# Microcontroller.net
KiCad netlist of a schematic drawn in Altium Designer
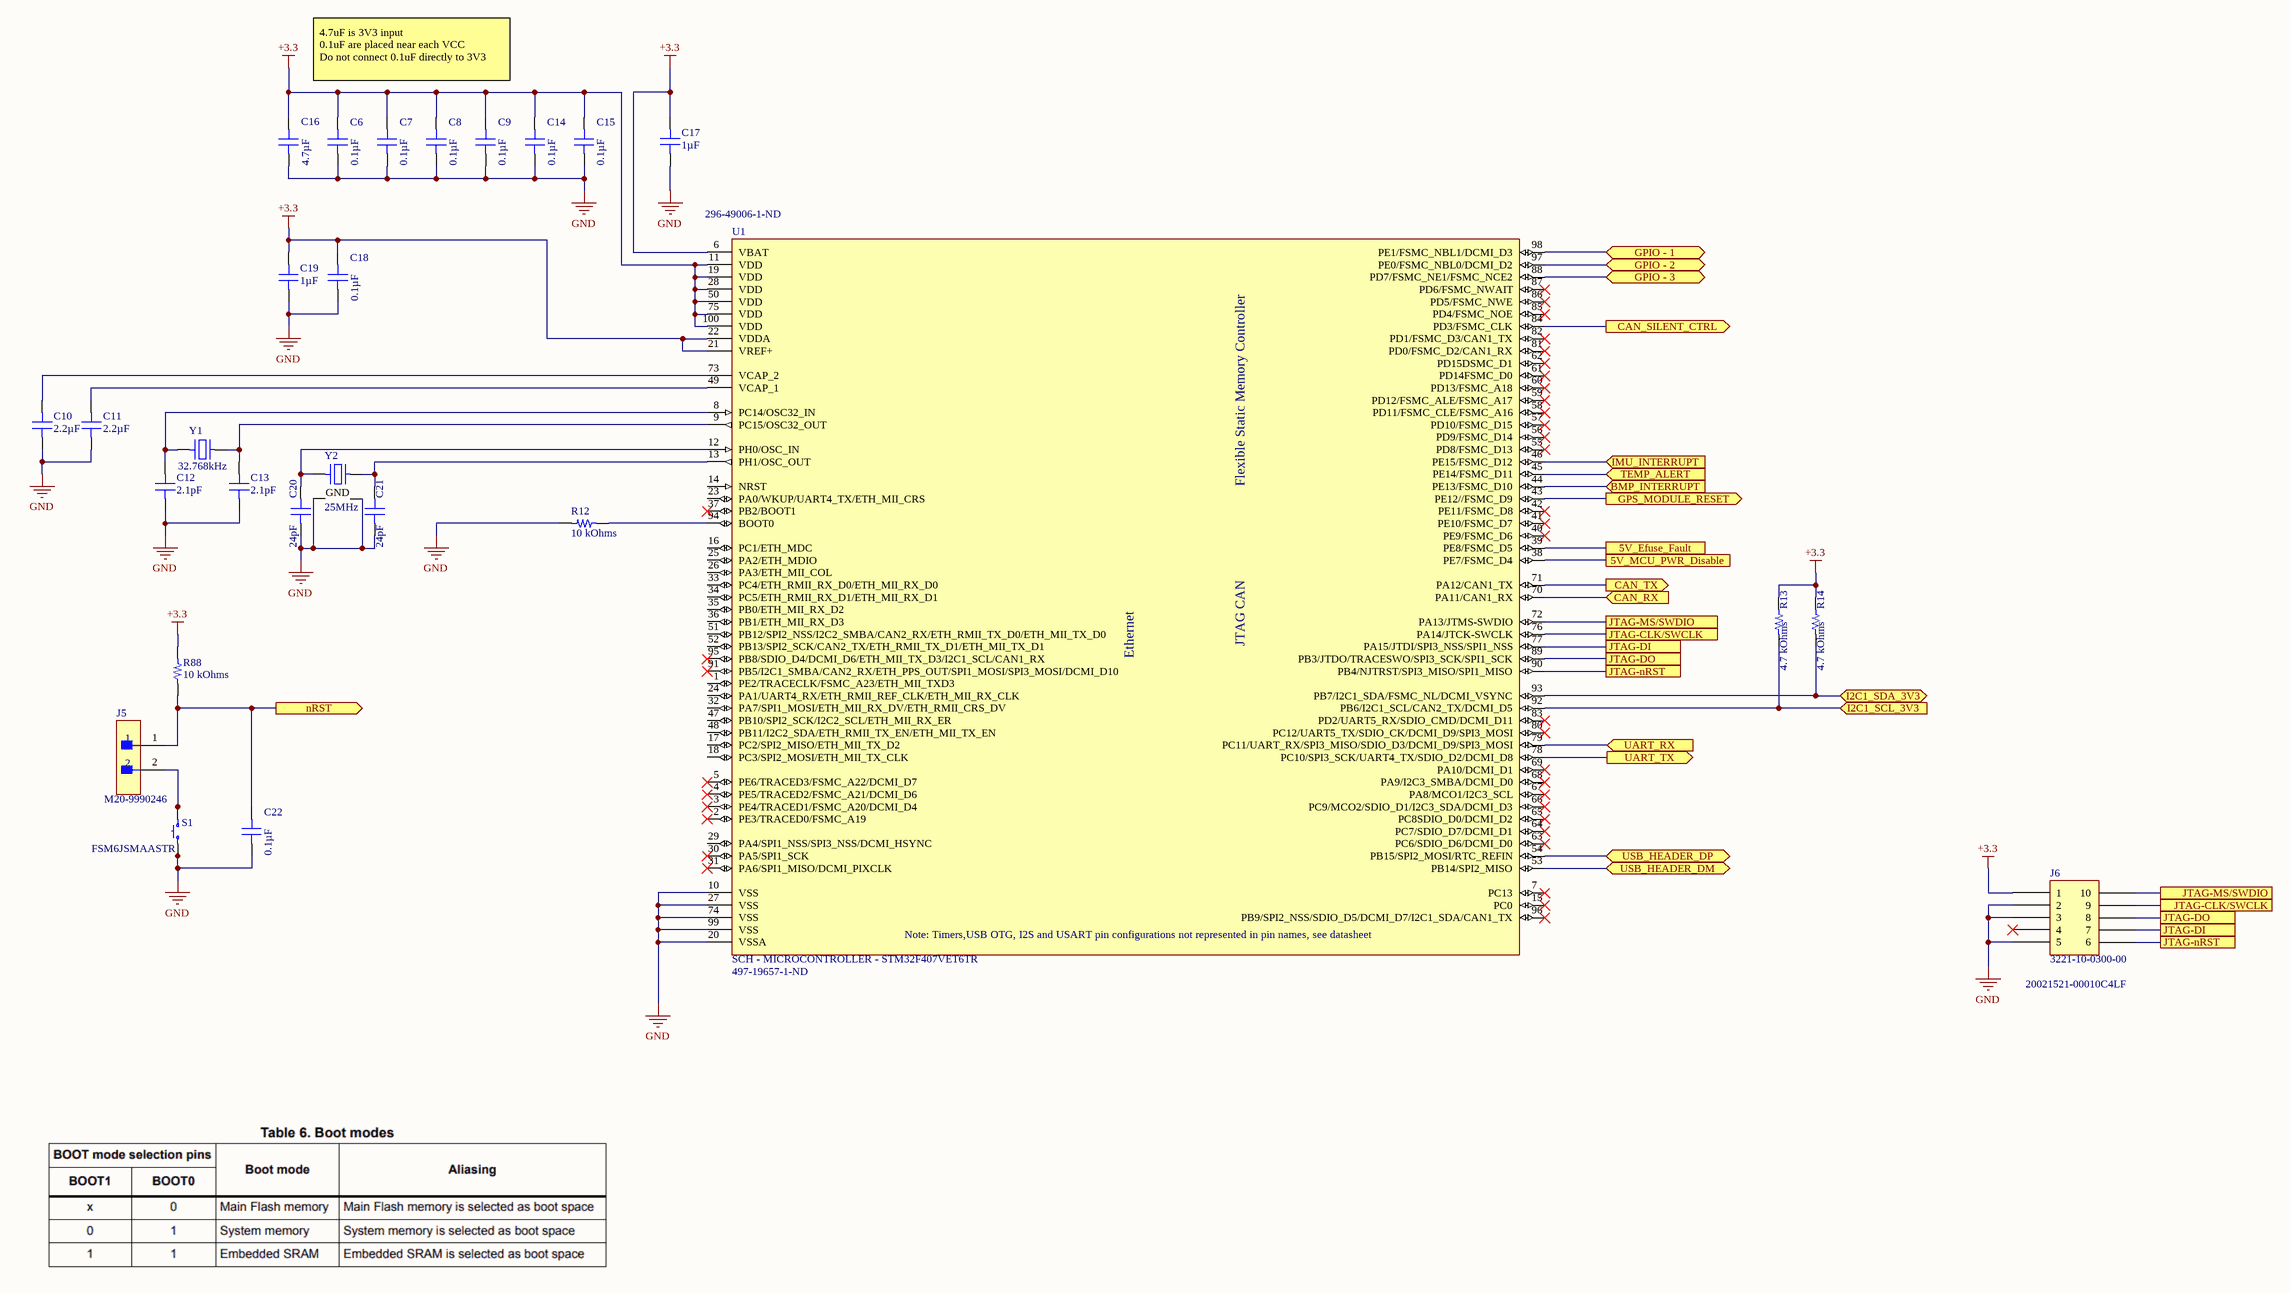
[diagram p0: Microcontroller.SchDoc]

(export (version "E")
  (design (tool "Eeschema 10.0.6"))
  (components
    (comp (ref "C6")
      (value "0.1µF")
      (footprint "CAP 0603_1608")
      (description "CAP CER 0.1UF 25V X7R 0603")
      (fields
        (field (name "PART NUMBER") "CL10B104KA8WPNC")
        (field (name "MANUFACTURER") "Samsung Electro-Mechanics")
      )
      (libsource (lib "Celestial Altium Library - altium_library") (part "Capacitor"))
    )
    (comp (ref "C7")
      (value "0.1µF")
      (footprint "CAP 0603_1608")
      (description "CAP CER 0.1UF 25V X7R 0603")
      (fields
        (field (name "PART NUMBER") "CL10B104KA8WPNC")
        (field (name "MANUFACTURER") "Samsung Electro-Mechanics")
      )
      (libsource (lib "Celestial Altium Library - altium_library") (part "Capacitor"))
    )
    (comp (ref "C8")
      (value "0.1µF")
      (footprint "CAP 0603_1608")
      (description "CAP CER 0.1UF 25V X7R 0603")
      (fields
        (field (name "PART NUMBER") "CL10B104KA8WPNC")
        (field (name "MANUFACTURER") "Samsung Electro-Mechanics")
      )
      (libsource (lib "Celestial Altium Library - altium_library") (part "Capacitor"))
    )
    (comp (ref "C9")
      (value "0.1µF")
      (footprint "CAP 0603_1608")
      (description "CAP CER 0.1UF 25V X7R 0603")
      (fields
        (field (name "PART NUMBER") "CL10B104KA8WPNC")
        (field (name "MANUFACTURER") "Samsung Electro-Mechanics")
      )
      (libsource (lib "Celestial Altium Library - altium_library") (part "Capacitor"))
    )
    (comp (ref "C10")
      (value "2.2µF")
      (footprint "CAP 0603_1608")
      (description "CAP CER 2.2UF 16V X5R 0603")
      (fields (field (name "PART NUMBER") "EMK107BJ225KA-T") (field (name "MANUFACTURER") "Taiyo Yuden"))
      (libsource (lib "Celestial Altium Library - altium_library") (part "Capacitor"))
    )
    (comp (ref "C11")
      (value "2.2µF")
      (footprint "CAP 0603_1608")
      (description "CAP CER 2.2UF 16V X5R 0603")
      (fields (field (name "PART NUMBER") "EMK107BJ225KA-T") (field (name "MANUFACTURER") "Taiyo Yuden"))
      (libsource (lib "Celestial Altium Library - altium_library") (part "Capacitor"))
    )
    (comp (ref "C12")
      (value "2.1pF")
      (footprint "CAP 0603_1608")
      (description "CAP CER RF 2.1PF 50V +/-0.1 PF C")
      (fields (field (name "PART NUMBER") "CBR06C219B5GAC") (field (name "MANUFACTURER") "KEMET"))
      (libsource (lib "Celestial Altium Library - altium_library") (part "Capacitor"))
    )
    (comp (ref "C13")
      (value "2.1pF")
      (footprint "CAP 0603_1608")
      (description "CAP CER RF 2.1PF 50V +/-0.1 PF C")
      (fields (field (name "PART NUMBER") "CBR06C219B5GAC") (field (name "MANUFACTURER") "KEMET"))
      (libsource (lib "Celestial Altium Library - altium_library") (part "Capacitor"))
    )
    (comp (ref "C14")
      (value "0.1µF")
      (footprint "CAP 0603_1608")
      (description "CAP CER 0.1UF 25V X7R 0603")
      (fields
        (field (name "PART NUMBER") "CL10B104KA8WPNC")
        (field (name "MANUFACTURER") "Samsung Electro-Mechanics")
      )
      (libsource (lib "Celestial Altium Library - altium_library") (part "Capacitor"))
    )
    (comp (ref "C15")
      (value "0.1µF")
      (footprint "CAP 0603_1608")
      (description "CAP CER 0.1UF 25V X7R 0603")
      (fields
        (field (name "PART NUMBER") "CL10B104KA8WPNC")
        (field (name "MANUFACTURER") "Samsung Electro-Mechanics")
      )
      (libsource (lib "Celestial Altium Library - altium_library") (part "Capacitor"))
    )
    (comp (ref "C16")
      (value "4.7µF")
      (footprint "CAP 0603_1608")
      (description "CAP CER 4.7UF 16V X5R 0603")
      (fields
        (field (name "PART NUMBER") "C1608X5R1C475K080AC")
        (field (name "MANUFACTURER") "TDK Corporation")
      )
      (libsource (lib "Celestial Altium Library - altium_library") (part "Capacitor"))
    )
    (comp (ref "C17")
      (value "1µF")
      (footprint "CAP 0603_1608")
      (description "CAP CER 1UF 16V X7R 0603")
      (fields
        (field (name "PART NUMBER") "GCM188R71C105KA64J")
        (field (name "MANUFACTURER") "Murata Electronics")
      )
      (libsource (lib "Celestial Altium Library - altium_library") (part "Capacitor"))
    )
    (comp (ref "C18")
      (value "0.1µF")
      (footprint "CAP 0603_1608")
      (description "CAP CER 0.1UF 25V X7R 0603")
      (fields
        (field (name "PART NUMBER") "CL10B104KA8WPNC")
        (field (name "MANUFACTURER") "Samsung Electro-Mechanics")
      )
      (libsource (lib "Celestial Altium Library - altium_library") (part "Capacitor"))
    )
    (comp (ref "C19")
      (value "1µF")
      (footprint "CAP 0603_1608")
      (description "CAP CER 1UF 16V X7R 0603")
      (fields
        (field (name "PART NUMBER") "GCM188R71C105KA64J")
        (field (name "MANUFACTURER") "Murata Electronics")
      )
      (libsource (lib "Celestial Altium Library - altium_library") (part "Capacitor"))
    )
    (comp (ref "C20")
      (value "24pF")
      (footprint "CAP 0603_1608")
      (description "CAP CER 24PF 50V C0G/NP0 0603")
      (fields
        (field (name "PART NUMBER") "CL10C240JB8NNNC")
        (field (name "MANUFACTURER") "Samsung Electro-Mechanics")
      )
      (libsource (lib "Celestial Altium Library - altium_library") (part "Capacitor"))
    )
    (comp (ref "C21")
      (value "24pF")
      (footprint "CAP 0603_1608")
      (description "CAP CER 24PF 50V C0G/NP0 0603")
      (fields
        (field (name "PART NUMBER") "CL10C240JB8NNNC")
        (field (name "MANUFACTURER") "Samsung Electro-Mechanics")
      )
      (libsource (lib "Celestial Altium Library - altium_library") (part "Capacitor"))
    )
    (comp (ref "C22")
      (value "0.1µF")
      (footprint "CAP 0603_1608")
      (description "CAP CER 0.1UF 25V X7R 0603")
      (fields
        (field (name "PART NUMBER") "CL10B104KA8WPNC")
        (field (name "MANUFACTURER") "Samsung Electro-Mechanics")
      )
      (libsource (lib "Celestial Altium Library - altium_library") (part "Capacitor"))
    )
    (comp (ref "J5")
      (value "M20-9990246")
      (footprint "FP-M20-9990246-MFG")
      (description "CONN HEADER VERT 2POS 2.54MM")
      (fields
        (field (name "OCTOPART") "https://octopart.com/m20-9990246-harwin-2590635")
        (field (name "MANUFACTURER") "Harwin")
      )
      (libsource (lib "Altium Content Vault") (part "3bc925449376181038e59eaffc5286c"))
    )
    (comp (ref "J6")
      (value "3221-10-0300-00")
      (footprint "CNC TECH 3221-10-0300-00")
      (description "CONN HEADER SMD 10POS 1.27MM")
      (fields (field (name "MANUFACTURER") "CNC Tech"))
      (libsource (lib "Celestial Altium Library - altium_library") (part "2x5 Pin"))
    )
    (comp (ref "R12")
      (value "10 kOhms")
      (footprint "RES 0603_1608")
      (description "RES 10K OHM 5% 1/10W 0603")
      (fields
        (field (name "PART NUMBER") "RMCF0603JT10K0")
        (field (name "MANUFACTURER") "Stackpole Electronics Inc")
      )
      (libsource (lib "Celestial Altium Library - altium_library") (part "Resistor"))
    )
    (comp (ref "R13")
      (value "4.7 kOhms")
      (footprint "RES 0603_1608")
      (description "RES 4.7K OHM 1% 1/10W 0603")
      (fields
        (field (name "PART NUMBER") "RMCF0603FT4K70")
        (field (name "MANUFACTURER") "Stackpole Electronics Inc")
      )
      (libsource (lib "Celestial Altium Library - altium_library") (part "Resistor"))
    )
    (comp (ref "R14")
      (value "4.7 kOhms")
      (footprint "RES 0603_1608")
      (description "RES 4.7K OHM 1% 1/10W 0603")
      (fields
        (field (name "PART NUMBER") "RMCF0603FT4K70")
        (field (name "MANUFACTURER") "Stackpole Electronics Inc")
      )
      (libsource (lib "Celestial Altium Library - altium_library") (part "Resistor"))
    )
    (comp (ref "R88")
      (value "10 kOhms")
      (footprint "RES 0603_1608")
      (description "RES 10K OHM 5% 1/10W 0603")
      (fields
        (field (name "PART NUMBER") "RMCF0603JT10K0")
        (field (name "MANUFACTURER") "Stackpole Electronics Inc")
      )
      (libsource (lib "Celestial Altium Library - altium_library") (part "Resistor"))
    )
    (comp (ref "S1")
      (value "FSM6JSMAASTR")
      (footprint "TE FSM6JSMA")
      (description "SWITCH TACTILE SPST-NO 0.05A 24V")
      (fields (field (name "MANUFACTURER") "TE Connectivity ALCOSWITCH Switches"))
      (libsource (lib "Celestial Altium Library - altium_library") (part "SPST-NO 4 PIN"))
    )
    (comp (ref "U1")
      (value "SCH - MICROCONTROLLER - STM32F407VET6TR")
      (footprint "PCB - LEADLESS - QFP - ST LQFP-100 14X14MM")
      (fields (field (name "SUPPLIER PART NUMBER 1") "497-19657-1-ND"))
      (libsource (lib "HAB_ICs") (part "SCH - MICROCONTROLLER - STM32F407VET6TR"))
    )
    (comp (ref "Y1")
      (value "32.768kHz")
      (footprint "ABRACON ABS07")
      (description "IOT 32.786KHZ XTAL")
      (fields
        (field (name "PART NUMBER") "ABS07-166-32.768KHZ-T")
        (field (name "MANUFACTURER") "Abracon LLC")
      )
      (libsource (lib "Celestial Altium Library - altium_library") (part "Abracon Crystal ABS07"))
    )
    (comp (ref "Y2")
      (value "25MHz")
      (footprint "EPSON TSX-3225")
      (description "CRYSTAL 25.0000MHZ 18PF SMD")
      (fields (field (name "PART NUMBER") "TSX-3225 25.0000MF20P-C0") (field (name "MANUFACTURER") "EPSON"))
      (libsource (lib "Celestial Altium Library - altium_library") (part "Epson Crystal TSX-3225"))
    )
  )
  (nets
    (net (code "1") (name "+3.3") (class "Default")
      (node (ref "C14") (pin "2") (pinfunction "2_2") (pintype "passive"))
      (node (ref "C15") (pin "2") (pinfunction "2_2") (pintype "passive"))
      (node (ref "C16") (pin "2") (pinfunction "2_2") (pintype "passive"))
      (node (ref "C17") (pin "2") (pinfunction "2_2") (pintype "passive"))
      (node (ref "C18") (pin "2") (pinfunction "2_2") (pintype "passive"))
      (node (ref "C19") (pin "2") (pinfunction "2_2") (pintype "passive"))
      (node (ref "C6") (pin "2") (pinfunction "2_2") (pintype "passive"))
      (node (ref "C7") (pin "2") (pinfunction "2_2") (pintype "passive"))
      (node (ref "C8") (pin "2") (pinfunction "2_2") (pintype "passive"))
      (node (ref "C9") (pin "2") (pinfunction "2_2") (pintype "passive"))
      (node (ref "J6") (pin "1") (pinfunction "1_1") (pintype "passive"))
      (node (ref "R13") (pin "2") (pinfunction "2_2") (pintype "passive"))
      (node (ref "R14") (pin "2") (pinfunction "2_2") (pintype "passive"))
      (node (ref "R88") (pin "1") (pinfunction "1_1") (pintype "passive"))
      (node (ref "U1") (pin "100") (pinfunction "VDD_100") (pintype "power_in"))
      (node (ref "U1") (pin "11") (pinfunction "VDD_11") (pintype "power_in"))
      (node (ref "U1") (pin "19") (pinfunction "VDD_19") (pintype "power_in"))
      (node (ref "U1") (pin "21") (pinfunction "VREF+_21") (pintype "power_in"))
      (node (ref "U1") (pin "22") (pinfunction "VDDA_22") (pintype "power_in"))
      (node (ref "U1") (pin "28") (pinfunction "VDD_28") (pintype "power_in"))
      (node (ref "U1") (pin "50") (pinfunction "VDD_50") (pintype "power_in"))
      (node (ref "U1") (pin "6") (pinfunction "VBAT_6") (pintype "power_in"))
      (node (ref "U1") (pin "75") (pinfunction "VDD_75") (pintype "power_in"))
    )
    (net (code "2") (name "/5V_Efuse_Fault") (class "Default")
      (node (ref "U1") (pin "39") (pinfunction "PE8/FSMC_D5_39") (pintype "bidirectional"))
    )
    (net (code "3") (name "/5V_MCU_PWR_Disable") (class "Default")
      (node (ref "U1") (pin "38") (pinfunction "PE7/FSMC_D4_38") (pintype "bidirectional"))
    )
    (net (code "4") (name "/BMP_INTERRUPT") (class "Default")
      (node (ref "U1") (pin "44") (pinfunction "PE13/FSMC_D10_44") (pintype "bidirectional"))
    )
    (net (code "5") (name "/CAN_RX") (class "Default")
      (node (ref "U1") (pin "70") (pinfunction "PA11/CAN1_RX_70") (pintype "bidirectional"))
    )
    (net (code "6") (name "/CAN_SILENT_CTRL") (class "Default")
      (node (ref "U1") (pin "84") (pinfunction "PD3/FSMC_CLK_84") (pintype "bidirectional"))
    )
    (net (code "7") (name "/CAN_TX") (class "Default")
      (node (ref "U1") (pin "71") (pinfunction "PA12/CAN1_TX_71") (pintype "bidirectional"))
    )
    (net (code "8") (name "/GPIO - 1") (class "Default")
      (node (ref "U1") (pin "98") (pinfunction "PE1/FSMC_NBL1/DCMI_D3_98") (pintype "bidirectional"))
    )
    (net (code "9") (name "/GPIO - 2") (class "Default")
      (node (ref "U1") (pin "97") (pinfunction "PE0/FSMC_NBL0/DCMI_D2_97") (pintype "bidirectional"))
    )
    (net (code "10") (name "/GPIO - 3") (class "Default")
      (node (ref "U1") (pin "88") (pinfunction "PD7/FSMC_NE1/FSMC_NCE2_88") (pintype "bidirectional"))
    )
    (net (code "11") (name "/GPS_MODULE_RESET") (class "Default")
      (node (ref "U1") (pin "43") (pinfunction "PE12//FSMC_D9_43") (pintype "bidirectional"))
    )
    (net (code "12") (name "/I2C1_SCL_3V3") (class "Default")
      (node (ref "R13") (pin "1") (pinfunction "1_1") (pintype "passive"))
      (node (ref "U1") (pin "92") (pinfunction "PB6/I2C1_SCL/CAN2_TX/DCMI_D5_92") (pintype "bidirectional"))
    )
    (net (code "13") (name "/I2C1_SDA_3V3") (class "Default")
      (node (ref "R14") (pin "1") (pinfunction "1_1") (pintype "passive"))
      (node (ref "U1") (pin "93") (pinfunction "PB7/I2C1_SDA/FSMC_NL/DCMI_VSYNC_93") (pintype "bidirectional"))
    )
    (net (code "14") (name "/IMU_INTERRUPT") (class "Default")
      (node (ref "U1") (pin "46") (pinfunction "PE15/FSMC_D12_46") (pintype "bidirectional"))
    )
    (net (code "15") (name "/JTAG-CLK{slash}SWCLK") (class "Default")
      (node (ref "J6") (pin "9") (pinfunction "9_9") (pintype "passive"))
      (node (ref "U1") (pin "76") (pinfunction "PA14/JTCK-SWCLK_76") (pintype "bidirectional"))
    )
    (net (code "16") (name "/JTAG-DI") (class "Default")
      (node (ref "J6") (pin "7") (pinfunction "7_7") (pintype "passive"))
      (node (ref "U1") (pin "77") (pinfunction "PA15/JTDI/SPI3_NSS/SPI1_NSS_77") (pintype "bidirectional"))
    )
    (net (code "17") (name "/JTAG-DO") (class "Default")
      (node (ref "J6") (pin "8") (pinfunction "8_8") (pintype "passive"))
      (node (ref "U1") (pin "89") (pinfunction "PB3/JTDO/TRACESWO/SPI3_SCK/SPI1_SCK_89") (pintype "bidirectional"))
    )
    (net (code "18") (name "/JTAG-MS{slash}SWDIO") (class "Default")
      (node (ref "J6") (pin "10") (pinfunction "10_10") (pintype "passive"))
      (node (ref "U1") (pin "72") (pinfunction "PA13/JTMS-SWDIO_72") (pintype "bidirectional"))
    )
    (net (code "19") (name "/JTAG-nRST") (class "Default")
      (node (ref "J6") (pin "6") (pinfunction "6_6") (pintype "passive"))
      (node (ref "U1") (pin "90") (pinfunction "PB4/NJTRST/SPI3_MISO/SPI1_MISO_90") (pintype "bidirectional"))
    )
    (net (code "20") (name "/TEMP_ALERT") (class "Default")
      (node (ref "U1") (pin "45") (pinfunction "PE14/FSMC_D11_45") (pintype "bidirectional"))
    )
    (net (code "21") (name "/UART_RX") (class "Default")
      (node (ref "U1") (pin "79") (pinfunction "PC11/UART_RX/SPI3_MISO/SDIO_D3/DCMI_D9/SPI3_MOSI_79") (pintype "bidirectional"))
    )
    (net (code "22") (name "/UART_TX") (class "Default")
      (node (ref "U1") (pin "78") (pinfunction "PC10/SPI3_SCK/UART4_TX/SDIO_D2/DCMI_D8_78") (pintype "bidirectional"))
    )
    (net (code "23") (name "/USB_HEADER_DM") (class "Default")
      (node (ref "U1") (pin "53") (pinfunction "PB14/SPI2_MISO_53") (pintype "bidirectional"))
    )
    (net (code "24") (name "/USB_HEADER_DP") (class "Default")
      (node (ref "U1") (pin "54") (pinfunction "PB15/SPI2_MOSI/RTC_REFIN_54") (pintype "bidirectional"))
    )
    (net (code "25") (name "/nRST") (class "Default")
      (node (ref "C22") (pin "2") (pinfunction "2_2") (pintype "passive"))
      (node (ref "J5") (pin "1") (pinfunction "1_1") (pintype "passive"))
      (node (ref "R88") (pin "2") (pinfunction "2_2") (pintype "passive"))
    )
    (net (code "26") (name "GND") (class "Default")
      (node (ref "C10") (pin "1") (pinfunction "1_1") (pintype "passive"))
      (node (ref "C11") (pin "1") (pinfunction "1_1") (pintype "passive"))
      (node (ref "C12") (pin "1") (pinfunction "1_1") (pintype "passive"))
      (node (ref "C13") (pin "1") (pinfunction "1_1") (pintype "passive"))
      (node (ref "C14") (pin "1") (pinfunction "1_1") (pintype "passive"))
      (node (ref "C15") (pin "1") (pinfunction "1_1") (pintype "passive"))
      (node (ref "C16") (pin "1") (pinfunction "1_1") (pintype "passive"))
      (node (ref "C17") (pin "1") (pinfunction "1_1") (pintype "passive"))
      (node (ref "C18") (pin "1") (pinfunction "1_1") (pintype "passive"))
      (node (ref "C19") (pin "1") (pinfunction "1_1") (pintype "passive"))
      (node (ref "C20") (pin "1") (pinfunction "1_1") (pintype "passive"))
      (node (ref "C21") (pin "1") (pinfunction "1_1") (pintype "passive"))
      (node (ref "C22") (pin "1") (pinfunction "1_1") (pintype "passive"))
      (node (ref "C6") (pin "1") (pinfunction "1_1") (pintype "passive"))
      (node (ref "C7") (pin "1") (pinfunction "1_1") (pintype "passive"))
      (node (ref "C8") (pin "1") (pinfunction "1_1") (pintype "passive"))
      (node (ref "C9") (pin "1") (pinfunction "1_1") (pintype "passive"))
      (node (ref "J6") (pin "2") (pinfunction "2_2") (pintype "passive"))
      (node (ref "J6") (pin "3") (pinfunction "3_3") (pintype "passive"))
      (node (ref "J6") (pin "5") (pinfunction "5_5") (pintype "passive"))
      (node (ref "R12") (pin "2") (pinfunction "2_2") (pintype "passive"))
      (node (ref "S1") (pin "1") (pinfunction "1_1") (pintype "passive"))
      (node (ref "S1") (pin "2") (pinfunction "2_2") (pintype "passive"))
      (node (ref "U1") (pin "10") (pinfunction "VSS_10") (pintype "power_in"))
      (node (ref "U1") (pin "20") (pinfunction "VSSA_20") (pintype "power_in"))
      (node (ref "U1") (pin "27") (pinfunction "VSS_27") (pintype "power_in"))
      (node (ref "U1") (pin "74") (pinfunction "VSS_74") (pintype "power_in"))
      (node (ref "U1") (pin "99") (pinfunction "VSS_99") (pintype "power_in"))
      (node (ref "Y2") (pin "2") (pinfunction "GND_2") (pintype "passive"))
      (node (ref "Y2") (pin "4") (pinfunction "GND_4") (pintype "passive"))
    )
    (net (code "27") (name "Net-(J5-Pad2)") (class "Default")
      (node (ref "J5") (pin "2") (pinfunction "2_2") (pintype "passive"))
      (node (ref "S1") (pin "3") (pinfunction "3_3") (pintype "passive"))
      (node (ref "S1") (pin "4") (pinfunction "4_4") (pintype "passive"))
    )
    (net (code "28") (name "Net-(U1-BOOT0)") (class "Default")
      (node (ref "R12") (pin "1") (pinfunction "1_1") (pintype "passive"))
      (node (ref "U1") (pin "94") (pinfunction "BOOT0_94") (pintype "bidirectional"))
    )
    (net (code "29") (name "Net-(U1-PC14{slash}OSC32_IN)") (class "Default")
      (node (ref "C12") (pin "2") (pinfunction "2_2") (pintype "passive"))
      (node (ref "U1") (pin "8") (pinfunction "PC14/OSC32_IN_8") (pintype "input"))
      (node (ref "Y1") (pin "1") (pinfunction "1_1") (pintype "passive"))
    )
    (net (code "30") (name "Net-(U1-PC15{slash}OSC32_OUT)") (class "Default")
      (node (ref "C13") (pin "2") (pinfunction "2_2") (pintype "passive"))
      (node (ref "U1") (pin "9") (pinfunction "PC15/OSC32_OUT_9") (pintype "output"))
      (node (ref "Y1") (pin "2") (pinfunction "2_2") (pintype "passive"))
    )
    (net (code "31") (name "Net-(U1-PH0{slash}OSC_IN)") (class "Default")
      (node (ref "C20") (pin "2") (pinfunction "2_2") (pintype "passive"))
      (node (ref "U1") (pin "12") (pinfunction "PH0/OSC_IN_12") (pintype "input"))
      (node (ref "Y2") (pin "1") (pinfunction "1_1") (pintype "passive"))
    )
    (net (code "32") (name "Net-(U1-PH1{slash}OSC_OUT)") (class "Default")
      (node (ref "C21") (pin "2") (pinfunction "2_2") (pintype "passive"))
      (node (ref "U1") (pin "13") (pinfunction "PH1/OSC_OUT_13") (pintype "output"))
      (node (ref "Y2") (pin "3") (pinfunction "3_3") (pintype "passive"))
    )
    (net (code "33") (name "Net-(U1-VCAP_1)") (class "Default")
      (node (ref "C11") (pin "2") (pinfunction "2_2") (pintype "passive"))
      (node (ref "U1") (pin "49") (pinfunction "VCAP_1_49") (pintype "power_in"))
    )
    (net (code "34") (name "Net-(U1-VCAP_2)") (class "Default")
      (node (ref "C10") (pin "2") (pinfunction "2_2") (pintype "passive"))
      (node (ref "U1") (pin "73") (pinfunction "VCAP_2_73") (pintype "power_in"))
    )
    (net (code "35") (name "unconnected-(J6-Pad4)") (class "Default")
      (node (ref "J6") (pin "4") (pinfunction "4_4") (pintype "passive+no_connect"))
    )
    (net (code "36") (name "unconnected-(U1-NRST-Pad14)") (class "Default")
      (node (ref "U1") (pin "14") (pinfunction "NRST_14") (pintype "input"))
    )
    (net (code "37") (name "unconnected-(U1-PA0{slash}WKUP{slash}UART4_TX{slash}ETH_MII_CRS-Pad23)") (class "Default")
      (node (ref "U1") (pin "23") (pinfunction "PA0/WKUP/UART4_TX/ETH_MII_CRS_23") (pintype "bidirectional"))
    )
    (net (code "38") (name "unconnected-(U1-PA1{slash}UART4_RX{slash}ETH_RMII_REF_CLK{slash}ETH_MII_RX_CLK-Pad24)") (class "Default")
      (node (ref "U1") (pin "24") (pinfunction "PA1/UART4_RX/ETH_RMII_REF_CLK/ETH_MII_RX_CLK_24") (pintype "bidirectional"))
    )
    (net (code "39") (name "unconnected-(U1-PA2{slash}ETH_MDIO-Pad25)") (class "Default")
      (node (ref "U1") (pin "25") (pinfunction "PA2/ETH_MDIO_25") (pintype "bidirectional"))
    )
    (net (code "40") (name "unconnected-(U1-PA3{slash}ETH_MII_COL-Pad26)") (class "Default")
      (node (ref "U1") (pin "26") (pinfunction "PA3/ETH_MII_COL_26") (pintype "bidirectional"))
    )
    (net (code "41") (name "unconnected-(U1-PA4{slash}SPI1_NSS{slash}SPI3_NSS{slash}DCMI_HSYNC-Pad29)") (class "Default")
      (node (ref "U1") (pin "29") (pinfunction "PA4/SPI1_NSS/SPI3_NSS/DCMI_HSYNC_29") (pintype "bidirectional"))
    )
    (net (code "42") (name "unconnected-(U1-PA5{slash}SPI1_SCK-Pad30)") (class "Default")
      (node (ref "U1") (pin "30") (pinfunction "PA5/SPI1_SCK_30") (pintype "bidirectional+no_connect"))
    )
    (net (code "43") (name "unconnected-(U1-PA6{slash}SPI1_MISO{slash}DCMI_PIXCLK-Pad31)") (class "Default")
      (node (ref "U1") (pin "31") (pinfunction "PA6/SPI1_MISO/DCMI_PIXCLK_31") (pintype "bidirectional+no_connect"))
    )
    (net (code "44") (name "unconnected-(U1-PA7{slash}SPI1_MOSI{slash}ETH_MII_RX_DV{slash}ETH_RMII_CRS_DV-Pad32)") (class "Default")
      (node (ref "U1") (pin "32") (pinfunction "PA7/SPI1_MOSI/ETH_MII_RX_DV/ETH_RMII_CRS_DV_32") (pintype "bidirectional"))
    )
    (net (code "45") (name "unconnected-(U1-PA8{slash}MCO1{slash}I2C3_SCL-Pad67)") (class "Default")
      (node (ref "U1") (pin "67") (pinfunction "PA8/MCO1/I2C3_SCL_67") (pintype "bidirectional+no_connect"))
    )
    (net (code "46") (name "unconnected-(U1-PA9{slash}I2C3_SMBA{slash}DCMI_D0-Pad68)") (class "Default")
      (node (ref "U1") (pin "68") (pinfunction "PA9/I2C3_SMBA/DCMI_D0_68") (pintype "bidirectional+no_connect"))
    )
    (net (code "47") (name "unconnected-(U1-PA10{slash}DCMI_D1-Pad69)") (class "Default")
      (node (ref "U1") (pin "69") (pinfunction "PA10/DCMI_D1_69") (pintype "bidirectional+no_connect"))
    )
    (net (code "48") (name "unconnected-(U1-PB0{slash}ETH_MII_RX_D2-Pad35)") (class "Default")
      (node (ref "U1") (pin "35") (pinfunction "PB0/ETH_MII_RX_D2_35") (pintype "bidirectional"))
    )
    (net (code "49") (name "unconnected-(U1-PB1{slash}ETH_MII_RX_D3-Pad36)") (class "Default")
      (node (ref "U1") (pin "36") (pinfunction "PB1/ETH_MII_RX_D3_36") (pintype "bidirectional"))
    )
    (net (code "50") (name "unconnected-(U1-PB2{slash}BOOT1-Pad37)") (class "Default")
      (node (ref "U1") (pin "37") (pinfunction "PB2/BOOT1_37") (pintype "bidirectional+no_connect"))
    )
    (net (code "51") (name "unconnected-(U1-PB5{slash}I2C1_SMBA{slash}CAN2_RX{slash}ETH_PPS_OUT{slash}SPI1_MOSI{slash}SPI3_MOSI{slash}DCMI_D10-Pad91)") (class "Default")
      (node (ref "U1") (pin "91") (pinfunction "PB5/I2C1_SMBA/CAN2_RX/ETH_PPS_OUT/SPI1_MOSI/SPI3_MOSI/DCMI_D10_91") (pintype "bidirectional+no_connect"))
    )
    (net (code "52") (name "unconnected-(U1-PB8{slash}SDIO_D4{slash}DCMI_D6{slash}ETH_MII_TX_D3{slash}I2C1_SCL{slash}CAN1_RX-Pad95)") (class "Default")
      (node (ref "U1") (pin "95") (pinfunction "PB8/SDIO_D4/DCMI_D6/ETH_MII_TX_D3/I2C1_SCL/CAN1_RX_95") (pintype "bidirectional+no_connect"))
    )
    (net (code "53") (name "unconnected-(U1-PB9{slash}SPI2_NSS{slash}SDIO_D5{slash}DCMI_D7{slash}I2C1_SDA{slash}CAN1_TX-Pad96)") (class "Default")
      (node (ref "U1") (pin "96") (pinfunction "PB9/SPI2_NSS/SDIO_D5/DCMI_D7/I2C1_SDA/CAN1_TX_96") (pintype "bidirectional+no_connect"))
    )
    (net (code "54") (name "unconnected-(U1-PB10{slash}SPI2_SCK{slash}I2C2_SCL{slash}ETH_MII_RX_ER-Pad47)") (class "Default")
      (node (ref "U1") (pin "47") (pinfunction "PB10/SPI2_SCK/I2C2_SCL/ETH_MII_RX_ER_47") (pintype "bidirectional"))
    )
    (net (code "55") (name "unconnected-(U1-PB11{slash}I2C2_SDA{slash}ETH_RMII_TX_EN{slash}ETH_MII_TX_EN-Pad48)") (class "Default")
      (node (ref "U1") (pin "48") (pinfunction "PB11/I2C2_SDA/ETH_RMII_TX_EN/ETH_MII_TX_EN_48") (pintype "bidirectional"))
    )
    (net (code "56") (name "unconnected-(U1-PB12{slash}SPI2_NSS{slash}I2C2_SMBA{slash}CAN2_RX{slash}ETH_RMII_TX_D0{slash}ETH_MII_TX_D0-Pad51)") (class "Default")
      (node (ref "U1") (pin "51") (pinfunction "PB12/SPI2_NSS/I2C2_SMBA/CAN2_RX/ETH_RMII_TX_D0/ETH_MII_TX_D0_51") (pintype "bidirectional"))
    )
    (net (code "57") (name "unconnected-(U1-PB13{slash}SPI2_SCK{slash}CAN2_TX{slash}ETH_RMII_TX_D1{slash}ETH_MII_TX_D1-Pad52)") (class "Default")
      (node (ref "U1") (pin "52") (pinfunction "PB13/SPI2_SCK/CAN2_TX/ETH_RMII_TX_D1/ETH_MII_TX_D1_52") (pintype "bidirectional"))
    )
    (net (code "58") (name "unconnected-(U1-PC0-Pad15)") (class "Default")
      (node (ref "U1") (pin "15") (pinfunction "PC0_15") (pintype "bidirectional+no_connect"))
    )
    (net (code "59") (name "unconnected-(U1-PC1{slash}ETH_MDC-Pad16)") (class "Default")
      (node (ref "U1") (pin "16") (pinfunction "PC1/ETH_MDC_16") (pintype "bidirectional"))
    )
    (net (code "60") (name "unconnected-(U1-PC2{slash}SPI2_MISO{slash}ETH_MII_TX_D2-Pad17)") (class "Default")
      (node (ref "U1") (pin "17") (pinfunction "PC2/SPI2_MISO/ETH_MII_TX_D2_17") (pintype "bidirectional"))
    )
    (net (code "61") (name "unconnected-(U1-PC3{slash}SPI2_MOSI{slash}ETH_MII_TX_CLK-Pad18)") (class "Default")
      (node (ref "U1") (pin "18") (pinfunction "PC3/SPI2_MOSI/ETH_MII_TX_CLK_18") (pintype "bidirectional"))
    )
    (net (code "62") (name "unconnected-(U1-PC4{slash}ETH_RMII_RX_D0{slash}ETH_MII_RX_D0-Pad33)") (class "Default")
      (node (ref "U1") (pin "33") (pinfunction "PC4/ETH_RMII_RX_D0/ETH_MII_RX_D0_33") (pintype "bidirectional"))
    )
    (net (code "63") (name "unconnected-(U1-PC5{slash}ETH_RMII_RX_D1{slash}ETH_MII_RX_D1-Pad34)") (class "Default")
      (node (ref "U1") (pin "34") (pinfunction "PC5/ETH_RMII_RX_D1/ETH_MII_RX_D1_34") (pintype "bidirectional"))
    )
    (net (code "64") (name "unconnected-(U1-PC6{slash}SDIO_D6{slash}DCMI_D0-Pad63)") (class "Default")
      (node (ref "U1") (pin "63") (pinfunction "PC6/SDIO_D6/DCMI_D0_63") (pintype "bidirectional+no_connect"))
    )
    (net (code "65") (name "unconnected-(U1-PC7{slash}SDIO_D7{slash}DCMI_D1-Pad64)") (class "Default")
      (node (ref "U1") (pin "64") (pinfunction "PC7/SDIO_D7/DCMI_D1_64") (pintype "bidirectional+no_connect"))
    )
    (net (code "66") (name "unconnected-(U1-PC8SDIO_D0{slash}DCMI_D2-Pad65)") (class "Default")
      (node (ref "U1") (pin "65") (pinfunction "PC8SDIO_D0/DCMI_D2_65") (pintype "bidirectional+no_connect"))
    )
    (net (code "67") (name "unconnected-(U1-PC9{slash}MCO2{slash}SDIO_D1{slash}I2C3_SDA{slash}DCMI_D3-Pad66)") (class "Default")
      (node (ref "U1") (pin "66") (pinfunction "PC9/MCO2/SDIO_D1/I2C3_SDA/DCMI_D3_66") (pintype "bidirectional+no_connect"))
    )
    (net (code "68") (name "unconnected-(U1-PC12{slash}UART5_TX{slash}SDIO_CK{slash}DCMI_D9{slash}SPI3_MOSI-Pad80)") (class "Default")
      (node (ref "U1") (pin "80") (pinfunction "PC12/UART5_TX/SDIO_CK/DCMI_D9/SPI3_MOSI_80") (pintype "bidirectional+no_connect"))
    )
    (net (code "69") (name "unconnected-(U1-PC13-Pad7)") (class "Default")
      (node (ref "U1") (pin "7") (pinfunction "PC13_7") (pintype "bidirectional+no_connect"))
    )
    (net (code "70") (name "unconnected-(U1-PD0{slash}FSMC_D2{slash}CAN1_RX-Pad81)") (class "Default")
      (node (ref "U1") (pin "81") (pinfunction "PD0/FSMC_D2/CAN1_RX_81") (pintype "bidirectional+no_connect"))
    )
    (net (code "71") (name "unconnected-(U1-PD1{slash}FSMC_D3{slash}CAN1_TX-Pad82)") (class "Default")
      (node (ref "U1") (pin "82") (pinfunction "PD1/FSMC_D3/CAN1_TX_82") (pintype "bidirectional+no_connect"))
    )
    (net (code "72") (name "unconnected-(U1-PD2{slash}UART5_RX{slash}SDIO_CMD{slash}DCMI_D11-Pad83)") (class "Default")
      (node (ref "U1") (pin "83") (pinfunction "PD2/UART5_RX/SDIO_CMD/DCMI_D11_83") (pintype "bidirectional+no_connect"))
    )
    (net (code "73") (name "unconnected-(U1-PD4{slash}FSMC_NOE-Pad85)") (class "Default")
      (node (ref "U1") (pin "85") (pinfunction "PD4/FSMC_NOE_85") (pintype "bidirectional+no_connect"))
    )
    (net (code "74") (name "unconnected-(U1-PD5{slash}FSMC_NWE-Pad86)") (class "Default")
      (node (ref "U1") (pin "86") (pinfunction "PD5/FSMC_NWE_86") (pintype "bidirectional+no_connect"))
    )
    (net (code "75") (name "unconnected-(U1-PD6{slash}FSMC_NWAIT-Pad87)") (class "Default")
      (node (ref "U1") (pin "87") (pinfunction "PD6/FSMC_NWAIT_87") (pintype "bidirectional+no_connect"))
    )
    (net (code "76") (name "unconnected-(U1-PD8{slash}FSMC_D13-Pad55)") (class "Default")
      (node (ref "U1") (pin "55") (pinfunction "PD8/FSMC_D13_55") (pintype "bidirectional+no_connect"))
    )
    (net (code "77") (name "unconnected-(U1-PD9{slash}FSMC_D14-Pad56)") (class "Default")
      (node (ref "U1") (pin "56") (pinfunction "PD9/FSMC_D14_56") (pintype "bidirectional+no_connect"))
    )
    (net (code "78") (name "unconnected-(U1-PD10{slash}FSMC_D15-Pad57)") (class "Default")
      (node (ref "U1") (pin "57") (pinfunction "PD10/FSMC_D15_57") (pintype "bidirectional+no_connect"))
    )
    (net (code "79") (name "unconnected-(U1-PD11{slash}FSMC_CLE{slash}FSMC_A16-Pad58)") (class "Default")
      (node (ref "U1") (pin "58") (pinfunction "PD11/FSMC_CLE/FSMC_A16_58") (pintype "bidirectional+no_connect"))
    )
    (net (code "80") (name "unconnected-(U1-PD12{slash}FSMC_ALE{slash}FSMC_A17-Pad59)") (class "Default")
      (node (ref "U1") (pin "59") (pinfunction "PD12/FSMC_ALE/FSMC_A17_59") (pintype "bidirectional+no_connect"))
    )
    (net (code "81") (name "unconnected-(U1-PD13{slash}FSMC_A18-Pad60)") (class "Default")
      (node (ref "U1") (pin "60") (pinfunction "PD13/FSMC_A18_60") (pintype "bidirectional+no_connect"))
    )
    (net (code "82") (name "unconnected-(U1-PD14FSMC_D0-Pad61)") (class "Default")
      (node (ref "U1") (pin "61") (pinfunction "PD14FSMC_D0_61") (pintype "bidirectional+no_connect"))
    )
    (net (code "83") (name "unconnected-(U1-PD15DSMC_D1-Pad62)") (class "Default")
      (node (ref "U1") (pin "62") (pinfunction "PD15DSMC_D1_62") (pintype "bidirectional+no_connect"))
    )
    (net (code "84") (name "unconnected-(U1-PE2{slash}TRACECLK{slash}FSMC_A23{slash}ETH_MII_TXD3-Pad1)") (class "Default")
      (node (ref "U1") (pin "1") (pinfunction "PE2/TRACECLK/FSMC_A23/ETH_MII_TXD3_1") (pintype "bidirectional"))
    )
    (net (code "85") (name "unconnected-(U1-PE3{slash}TRACED0{slash}FSMC_A19-Pad2)") (class "Default")
      (node (ref "U1") (pin "2") (pinfunction "PE3/TRACED0/FSMC_A19_2") (pintype "bidirectional+no_connect"))
    )
    (net (code "86") (name "unconnected-(U1-PE4{slash}TRACED1{slash}FSMC_A20{slash}DCMI_D4-Pad3)") (class "Default")
      (node (ref "U1") (pin "3") (pinfunction "PE4/TRACED1/FSMC_A20/DCMI_D4_3") (pintype "bidirectional+no_connect"))
    )
    (net (code "87") (name "unconnected-(U1-PE5{slash}TRACED2{slash}FSMC_A21{slash}DCMI_D6-Pad4)") (class "Default")
      (node (ref "U1") (pin "4") (pinfunction "PE5/TRACED2/FSMC_A21/DCMI_D6_4") (pintype "bidirectional+no_connect"))
    )
    (net (code "88") (name "unconnected-(U1-PE6{slash}TRACED3{slash}FSMC_A22{slash}DCMI_D7-Pad5)") (class "Default")
      (node (ref "U1") (pin "5") (pinfunction "PE6/TRACED3/FSMC_A22/DCMI_D7_5") (pintype "bidirectional+no_connect"))
    )
    (net (code "89") (name "unconnected-(U1-PE9{slash}FSMC_D6-Pad40)") (class "Default")
      (node (ref "U1") (pin "40") (pinfunction "PE9/FSMC_D6_40") (pintype "bidirectional+no_connect"))
    )
    (net (code "90") (name "unconnected-(U1-PE10{slash}FSMC_D7-Pad41)") (class "Default")
      (node (ref "U1") (pin "41") (pinfunction "PE10/FSMC_D7_41") (pintype "bidirectional+no_connect"))
    )
    (net (code "91") (name "unconnected-(U1-PE11{slash}FSMC_D8-Pad42)") (class "Default")
      (node (ref "U1") (pin "42") (pinfunction "PE11/FSMC_D8_42") (pintype "bidirectional+no_connect"))
    )
  )
)
